# Escorna_CPU_2_12.net
KiCad netlist of a schematic drawn in EAGLE
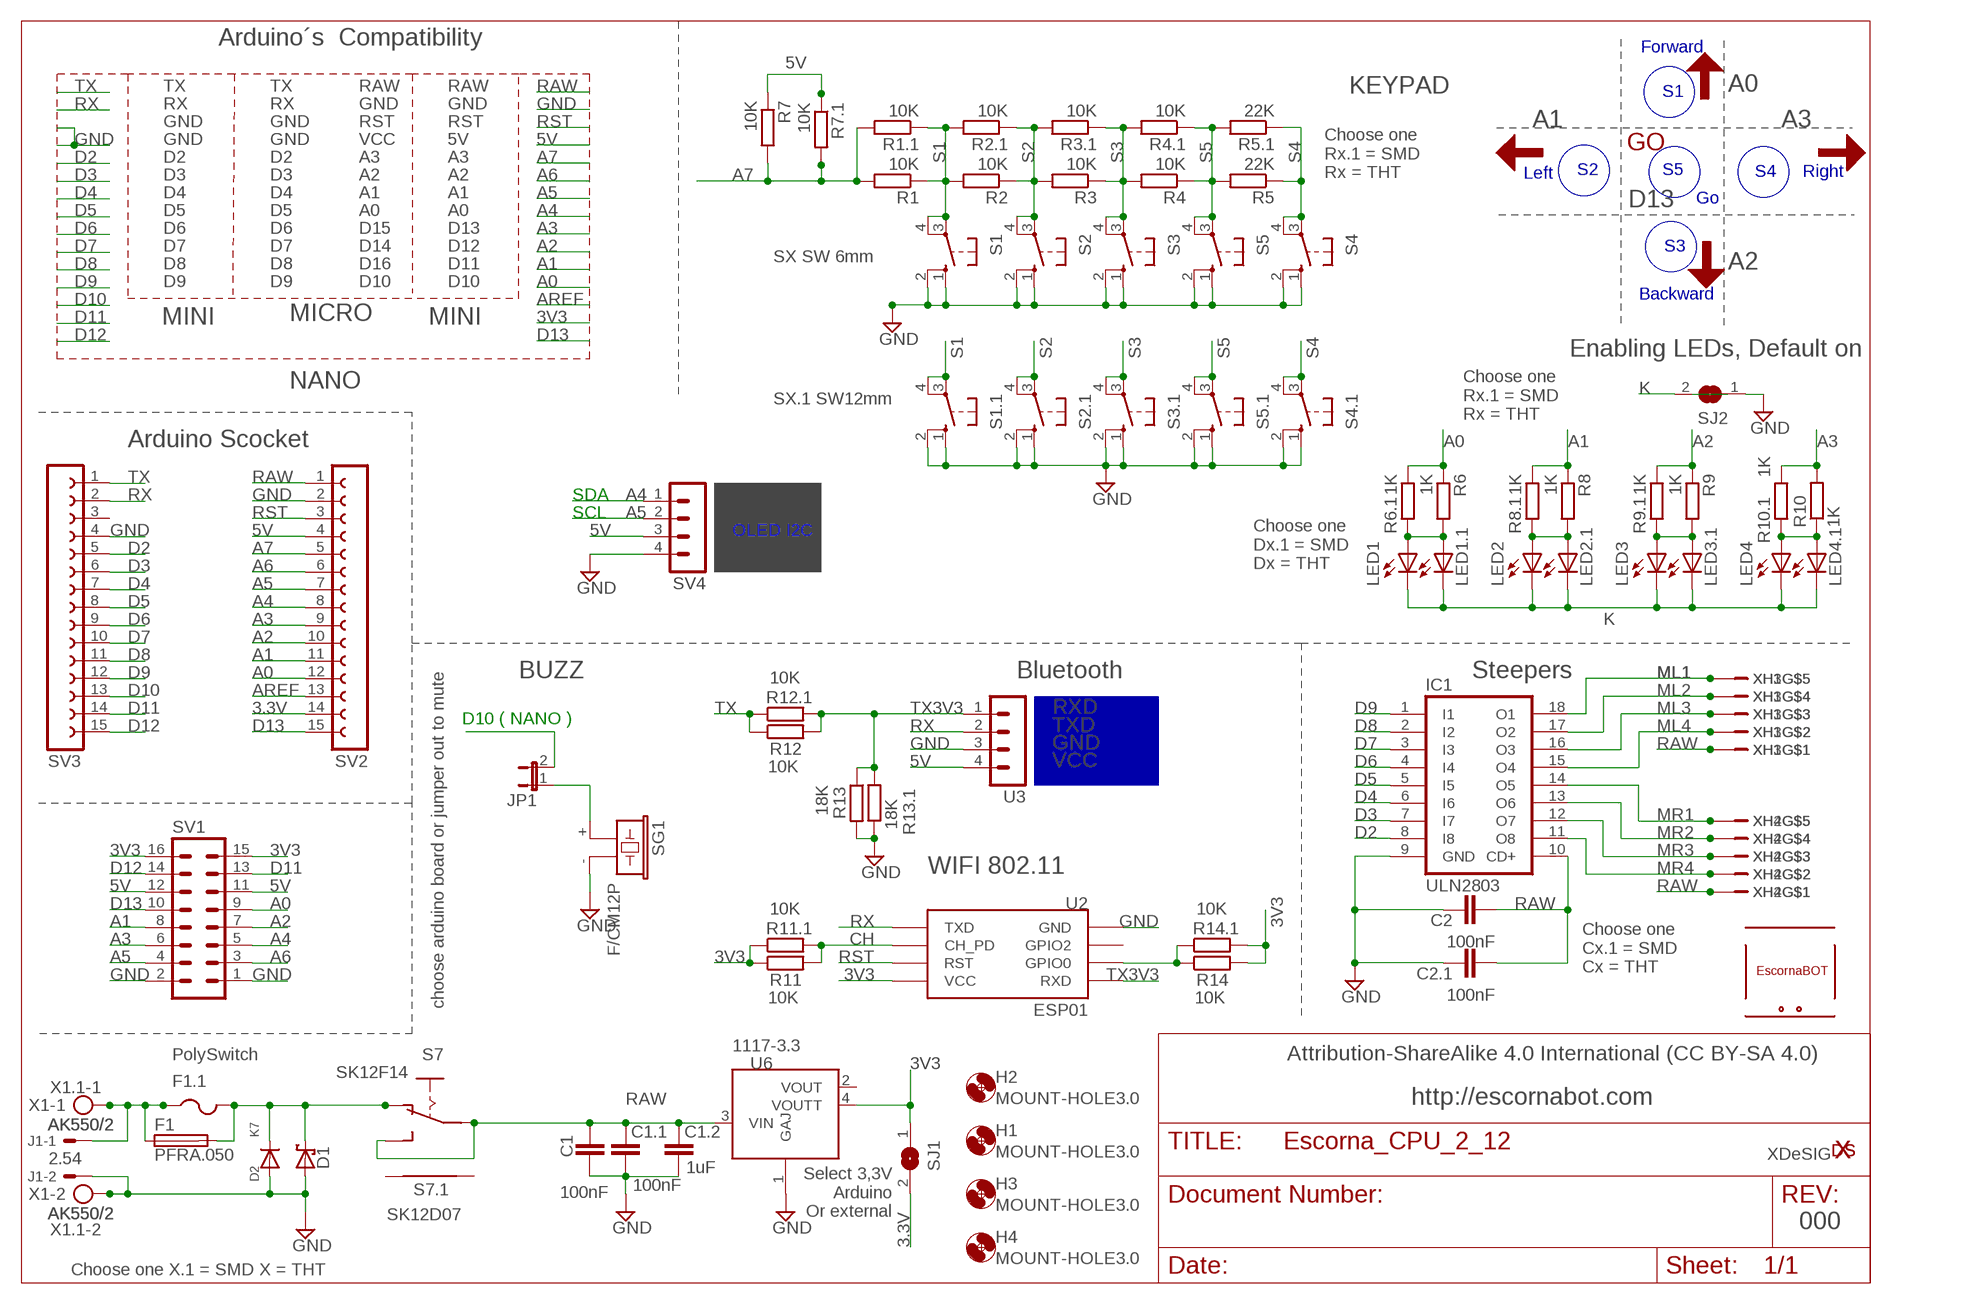
[diagram p0: schematic, sheet 1]

(export (version "E")
  (design (tool "Eeschema 10.0.6"))
  (components
    (comp (ref "C1")
      (value "100nF")
      (footprint "eagle-import:C025-025X050")
      (libsource (lib "eagle-import") (part "C-EU025-025X050"))
    )
    (comp (ref "C1.1")
      (value "100nF")
      (footprint "eagle-import:C1206")
      (libsource (lib "eagle-import") (part "C-EUC1206"))
    )
    (comp (ref "C1.2")
      (value "1uF")
      (footprint "eagle-import:C1206")
      (libsource (lib "eagle-import") (part "C-EUC1206"))
    )
    (comp (ref "C2")
      (value "100nF")
      (footprint "eagle-import:C025-025X050")
      (libsource (lib "eagle-import") (part "C-EU025-025X050"))
    )
    (comp (ref "C2.1")
      (value "100nF")
      (footprint "eagle-import:C1206")
      (libsource (lib "eagle-import") (part "C-EUC1206"))
    )
    (comp (ref "D1")
      (value "1N5817")
      (footprint "eagle-import:DO41-10")
      (libsource (lib "eagle-import") (part "P4KEXX"))
    )
    (comp (ref "D2")
      (value "K7")
      (footprint "eagle-import:SMADIODE")
      (libsource (lib "eagle-import") (part "DIODESMA"))
    )
    (comp (ref "ESC")
      (value "ESCORNABOT")
      (footprint "eagle-import:ESCORNA_PEQUE")
      (libsource (lib "eagle-import") (part "ESCORNABOT"))
    )
    (comp (ref "F1")
      (value "PFRA.050")
      (footprint "eagle-import:TE5")
      (libsource (lib "eagle-import") (part "FUSETE5"))
    )
    (comp (ref "F1.1")
      (value "PolySwitch")
      (footprint "eagle-import:R1206")
      (libsource (lib "eagle-import") (part "PTCFUSE-1206"))
    )
    (comp (ref "H1")
      (value "MOUNT-HOLE3.0")
      (footprint "eagle-import:3,0")
      (libsource (lib "eagle-import") (part "MOUNT-HOLE3.0"))
    )
    (comp (ref "H2")
      (value "MOUNT-HOLE3.0")
      (footprint "eagle-import:3,0")
      (libsource (lib "eagle-import") (part "MOUNT-HOLE3.0"))
    )
    (comp (ref "H3")
      (value "MOUNT-HOLE3.0")
      (footprint "eagle-import:3,0")
      (libsource (lib "eagle-import") (part "MOUNT-HOLE3.0"))
    )
    (comp (ref "H4")
      (value "MOUNT-HOLE3.0")
      (footprint "eagle-import:3,0")
      (libsource (lib "eagle-import") (part "MOUNT-HOLE3.0"))
    )
    (comp (ref "IC1")
      (value "ULN2803")
      (footprint "eagle-import:DIL18")
      (libsource (lib "eagle-import") (part "ULN2803A"))
    )
    (comp (ref "J1")
      (value "2.54")
      (footprint "eagle-import:6410-02")
      (libsource (lib "eagle-import") (part "22-?-0227-2021"))
    )
    (comp (ref "JP1")
      (value "JP1E")
      (footprint "eagle-import:JP1")
      (libsource (lib "eagle-import") (part "JP1E"))
    )
    (comp (ref "LED1")
      (value "LED3MM")
      (footprint "eagle-import:LED3MM")
      (libsource (lib "eagle-import") (part "LED3MM"))
    )
    (comp (ref "LED1.1")
      (value "LEDCHIPLED_0603")
      (footprint "eagle-import:CHIPLED_0603")
      (libsource (lib "eagle-import") (part "LEDCHIPLED_0603"))
    )
    (comp (ref "LED2")
      (value "LED3MM")
      (footprint "eagle-import:LED3MM")
      (libsource (lib "eagle-import") (part "LED3MM"))
    )
    (comp (ref "LED2.1")
      (value "LEDCHIPLED_0603")
      (footprint "eagle-import:CHIPLED_0603")
      (libsource (lib "eagle-import") (part "LEDCHIPLED_0603"))
    )
    (comp (ref "LED3")
      (value "LED3MM")
      (footprint "eagle-import:LED3MM")
      (libsource (lib "eagle-import") (part "LED3MM"))
    )
    (comp (ref "LED3.1")
      (value "LEDCHIPLED_0603")
      (footprint "eagle-import:CHIPLED_0603")
      (libsource (lib "eagle-import") (part "LEDCHIPLED_0603"))
    )
    (comp (ref "LED4")
      (value "LED3MM")
      (footprint "eagle-import:LED3MM")
      (libsource (lib "eagle-import") (part "LED3MM"))
    )
    (comp (ref "LED4.1")
      (value "LEDCHIPLED_0603")
      (footprint "eagle-import:CHIPLED_0603")
      (libsource (lib "eagle-import") (part "LEDCHIPLED_0603"))
    )
    (comp (ref "R1")
      (value "10K")
      (footprint "eagle-import:0204_7")
      (libsource (lib "eagle-import") (part "R-EU_0204/7"))
    )
    (comp (ref "R1.1")
      (value "10K")
      (footprint "eagle-import:R0603")
      (libsource (lib "eagle-import") (part "R-EU_R0603"))
    )
    (comp (ref "R2")
      (value "10K")
      (footprint "eagle-import:0204_7")
      (libsource (lib "eagle-import") (part "R-EU_0204/7"))
    )
    (comp (ref "R2.1")
      (value "10K")
      (footprint "eagle-import:R0603")
      (libsource (lib "eagle-import") (part "R-EU_R0603"))
    )
    (comp (ref "R3")
      (value "10K")
      (footprint "eagle-import:0204_7")
      (libsource (lib "eagle-import") (part "R-EU_0204/7"))
    )
    (comp (ref "R3.1")
      (value "10K")
      (footprint "eagle-import:R0603")
      (libsource (lib "eagle-import") (part "R-EU_R0603"))
    )
    (comp (ref "R4")
      (value "10K")
      (footprint "eagle-import:0204_7")
      (libsource (lib "eagle-import") (part "R-EU_0204/7"))
    )
    (comp (ref "R4.1")
      (value "10K")
      (footprint "eagle-import:R0603")
      (libsource (lib "eagle-import") (part "R-EU_R0603"))
    )
    (comp (ref "R5")
      (value "22K")
      (footprint "eagle-import:0204_7")
      (libsource (lib "eagle-import") (part "R-EU_0204/7"))
    )
    (comp (ref "R5.1")
      (value "22K")
      (footprint "eagle-import:R0603")
      (libsource (lib "eagle-import") (part "R-EU_R0603"))
    )
    (comp (ref "R6")
      (value "1K")
      (footprint "eagle-import:0204_7")
      (libsource (lib "eagle-import") (part "R-EU_0204/7"))
    )
    (comp (ref "R6.1")
      (value "1K")
      (footprint "eagle-import:R0603")
      (libsource (lib "eagle-import") (part "R-EU_R0603"))
    )
    (comp (ref "R7")
      (value "10K")
      (footprint "eagle-import:0204_7")
      (libsource (lib "eagle-import") (part "R-EU_0204/7"))
    )
    (comp (ref "R7.1")
      (value "10K")
      (footprint "eagle-import:R0603")
      (libsource (lib "eagle-import") (part "R-EU_R0603"))
    )
    (comp (ref "R8")
      (value "1K")
      (footprint "eagle-import:0204_7")
      (libsource (lib "eagle-import") (part "R-EU_0204/7"))
    )
    (comp (ref "R8.1")
      (value "1K")
      (footprint "eagle-import:R0603")
      (libsource (lib "eagle-import") (part "R-EU_R0603"))
    )
    (comp (ref "R9")
      (value "1K")
      (footprint "eagle-import:0204_7")
      (libsource (lib "eagle-import") (part "R-EU_0204/7"))
    )
    (comp (ref "R9.1")
      (value "1K")
      (footprint "eagle-import:R0603")
      (libsource (lib "eagle-import") (part "R-EU_R0603"))
    )
    (comp (ref "R10")
      (value "1K")
      (footprint "eagle-import:0204_7")
      (libsource (lib "eagle-import") (part "R-EU_0204/7"))
    )
    (comp (ref "R10.1")
      (value "1K")
      (footprint "eagle-import:R0603")
      (libsource (lib "eagle-import") (part "R-EU_R0603"))
    )
    (comp (ref "R11")
      (value "10K")
      (footprint "eagle-import:0204_7")
      (libsource (lib "eagle-import") (part "R-EU_0204/7"))
    )
    (comp (ref "R11.1")
      (value "10K")
      (footprint "eagle-import:R0603")
      (libsource (lib "eagle-import") (part "R-EU_R0603"))
    )
    (comp (ref "R12")
      (value "10K")
      (footprint "eagle-import:0204_7")
      (libsource (lib "eagle-import") (part "R-EU_0204/7"))
    )
    (comp (ref "R12.1")
      (value "10K")
      (footprint "eagle-import:R0603")
      (libsource (lib "eagle-import") (part "R-EU_R0603"))
    )
    (comp (ref "R13")
      (value "18K")
      (footprint "eagle-import:0204_7")
      (libsource (lib "eagle-import") (part "R-EU_0204/7"))
    )
    (comp (ref "R13.1")
      (value "18K")
      (footprint "eagle-import:R0603")
      (libsource (lib "eagle-import") (part "R-EU_R0603"))
    )
    (comp (ref "R14")
      (value "10K")
      (footprint "eagle-import:0204_7")
      (libsource (lib "eagle-import") (part "R-EU_0204/7"))
    )
    (comp (ref "R14.1")
      (value "10K")
      (footprint "eagle-import:R0603")
      (libsource (lib "eagle-import") (part "R-EU_R0603"))
    )
    (comp (ref "S1")
      (value "10-XX")
      (footprint "eagle-import:B3F-10XX")
      (fields (field (name "MPN") "B3F-1000"))
      (libsource (lib "eagle-import") (part "10-XX"))
    )
    (comp (ref "S1.1")
      (value "40-XX")
      (footprint "eagle-import:B3F-40XX")
      (fields (field (name "MF") "OMRON COMPONENTS USA") (field (name "MPN") "B3F-4000"))
      (libsource (lib "eagle-import") (part "40-XX"))
    )
    (comp (ref "S2")
      (value "10-XX")
      (footprint "eagle-import:B3F-10XX")
      (fields (field (name "MPN") "B3F-1000"))
      (libsource (lib "eagle-import") (part "10-XX"))
    )
    (comp (ref "S2.1")
      (value "40-XX")
      (footprint "eagle-import:B3F-40XX")
      (fields (field (name "MF") "OMRON COMPONENTS USA") (field (name "MPN") "B3F-4000"))
      (libsource (lib "eagle-import") (part "40-XX"))
    )
    (comp (ref "S3")
      (value "10-XX")
      (footprint "eagle-import:B3F-10XX")
      (fields (field (name "MPN") "B3F-1000"))
      (libsource (lib "eagle-import") (part "10-XX"))
    )
    (comp (ref "S3.1")
      (value "40-XX")
      (footprint "eagle-import:B3F-40XX")
      (fields (field (name "MF") "OMRON COMPONENTS USA") (field (name "MPN") "B3F-4000"))
      (libsource (lib "eagle-import") (part "40-XX"))
    )
    (comp (ref "S4")
      (value "10-XX")
      (footprint "eagle-import:B3F-10XX")
      (fields (field (name "MPN") "B3F-1000"))
      (libsource (lib "eagle-import") (part "10-XX"))
    )
    (comp (ref "S4.1")
      (value "40-XX")
      (footprint "eagle-import:B3F-40XX")
      (fields (field (name "MF") "OMRON COMPONENTS USA") (field (name "MPN") "B3F-4000"))
      (libsource (lib "eagle-import") (part "40-XX"))
    )
    (comp (ref "S5")
      (value "10-XX")
      (footprint "eagle-import:B3F-10XX")
      (fields (field (name "MPN") "B3F-1000"))
      (libsource (lib "eagle-import") (part "10-XX"))
    )
    (comp (ref "S5.1")
      (value "40-XX")
      (footprint "eagle-import:B3F-40XX")
      (fields (field (name "MF") "OMRON COMPONENTS USA") (field (name "MPN") "B3F-4000"))
      (libsource (lib "eagle-import") (part "40-XX"))
    )
    (comp (ref "S7")
      (value "SK12F14")
      (footprint "eagle-import:ESCORNA_SK-12F14-G")
      (libsource (lib "eagle-import") (part "ESCORNA_SK12F14F"))
    )
    (comp (ref "S7.1")
      (value "SK12D07")
      (footprint "eagle-import:ESCORNA_SK-12D07")
      (libsource (lib "eagle-import") (part "ESCORNA_SK12F14D"))
    )
    (comp (ref "SG1")
      (value "F/CM12P")
      (footprint "eagle-import:F_CM12P")
      (libsource (lib "eagle-import") (part "F/CM12P"))
    )
    (comp (ref "SJ1") (value "SJ") (footprint "eagle-import:SJ") (libsource (lib "eagle-import") (part "SJ")))
    (comp (ref "SJ2") (value "SJ") (footprint "eagle-import:SJ") (libsource (lib "eagle-import") (part "SJ")))
    (comp (ref "SV1")
      (value "MA08-2")
      (footprint "eagle-import:MA08-2")
      (libsource (lib "eagle-import") (part "MA08-2"))
    )
    (comp (ref "SV2")
      (value "CON-LSTA_FE15-1")
      (footprint "eagle-import:CON-LSTA_FE15")
      (libsource (lib "eagle-import") (part "CON-LSTA_FE15-1"))
    )
    (comp (ref "SV3")
      (value "CON-LSTA_FE15-1")
      (footprint "eagle-import:CON-LSTA_FE15")
      (libsource (lib "eagle-import") (part "CON-LSTA_FE15-1"))
    )
    (comp (ref "SV4")
      (value "MA04-1")
      (footprint "eagle-import:MA04-1")
      (libsource (lib "eagle-import") (part "MA04-1"))
    )
    (comp (ref "U$1")
      (value "FRECHA")
      (footprint "eagle-import:FRECHA")
      (libsource (lib "eagle-import") (part "FRECHA"))
    )
    (comp (ref "U$2")
      (value "GO")
      (footprint "eagle-import:VALE")
      (libsource (lib "eagle-import") (part "GO"))
    )
    (comp (ref "U$3")
      (value "FRECHA")
      (footprint "eagle-import:FRECHA")
      (libsource (lib "eagle-import") (part "FRECHA"))
    )
    (comp (ref "U$6")
      (value "FRECHA")
      (footprint "eagle-import:FRECHA")
      (libsource (lib "eagle-import") (part "FRECHA"))
    )
    (comp (ref "U$11")
      (value "FRECHA")
      (footprint "eagle-import:FRECHA")
      (libsource (lib "eagle-import") (part "FRECHA"))
    )
    (comp (ref "U$13")
      (value "XDESIG_XDESIG21")
      (footprint "eagle-import:XDESIG_XDESIG")
      (libsource (lib "eagle-import") (part "XDESIG_XDESIG21"))
    )
    (comp (ref "U2")
      (value "ESP01")
      (footprint "eagle-import:ESP01")
      (libsource (lib "eagle-import") (part "ESP01"))
    )
    (comp (ref "U3")
      (value "MA04-1")
      (footprint "eagle-import:MA04-1")
      (libsource (lib "eagle-import") (part "MA04-1"))
    )
    (comp (ref "U6")
      (value "1117-3.3")
      (footprint "eagle-import:SOT223")
      (libsource (lib "eagle-import") (part "ASM1117-3.3"))
    )
    (comp (ref "X1")
      (value "AK550/2")
      (footprint "eagle-import:AK550_2")
      (libsource (lib "eagle-import") (part "AK550/2"))
    )
    (comp (ref "X1.1")
      (value "AK550/2")
      (footprint "eagle-import:AK550_2")
      (fields (field (name "OC_FARNELL") "unknown") (field (name "OC_NEWARK") "unknown"))
      (libsource (lib "eagle-import") (part "AK550/2"))
    )
    (comp (ref "XDS1")
      (value "XDESIG")
      (footprint "eagle-import:XDESIG_CU_2")
      (libsource (lib "eagle-import") (part "XDESIG"))
    )
    (comp (ref "XH1")
      (value "B5B-XH-A")
      (footprint "eagle-import:B5B-XH-A")
      (libsource (lib "eagle-import") (part "B5B-XH-A"))
    )
    (comp (ref "XH2")
      (value "B5B-XH-A")
      (footprint "eagle-import:B5B-XH-A")
      (libsource (lib "eagle-import") (part "B5B-XH-A"))
    )
    (comp (ref "XH3")
      (value "B5B-XH-A")
      (footprint "eagle-import:B5B-XH-A")
      (libsource (lib "eagle-import") (part "B5B-XH-A"))
    )
    (comp (ref "XH4")
      (value "B5B-XH-A")
      (footprint "eagle-import:B5B-XH-A")
      (libsource (lib "eagle-import") (part "B5B-XH-A"))
    )
  )
  (nets
    (net (code "1") (name "/3.3V") (class "Default")
      (node (ref "SJ1") (pin "2") (pinfunction "2_2") (pintype "passive"))
      (node (ref "SV2") (pin "14") (pinfunction "14_14") (pintype "passive"))
    )
    (net (code "2") (name "/3V3") (class "Default")
      (node (ref "R11") (pin "1") (pinfunction "1_1") (pintype "passive"))
      (node (ref "R11.1") (pin "1") (pinfunction "1_1") (pintype "passive"))
      (node (ref "R14") (pin "2") (pinfunction "2_2") (pintype "passive"))
      (node (ref "R14.1") (pin "2") (pinfunction "2_2") (pintype "passive"))
      (node (ref "SJ1") (pin "1") (pinfunction "1_1") (pintype "passive"))
      (node (ref "SV1") (pin "15") (pinfunction "15_15") (pintype "passive"))
      (node (ref "SV1") (pin "16") (pinfunction "16_16") (pintype "passive"))
      (node (ref "U2") (pin "VCC") (pinfunction "VCC_VCC") (pintype "bidirectional"))
      (node (ref "U6") (pin "4") (pinfunction "VOUTT_4") (pintype "bidirectional"))
    )
    (net (code "3") (name "/5V") (class "Default")
      (node (ref "R7") (pin "1") (pinfunction "1_1") (pintype "passive"))
      (node (ref "R7.1") (pin "1") (pinfunction "1_1") (pintype "passive"))
      (node (ref "SV1") (pin "11") (pinfunction "11_11") (pintype "passive"))
      (node (ref "SV1") (pin "12") (pinfunction "12_12") (pintype "passive"))
      (node (ref "SV2") (pin "4") (pinfunction "4_4") (pintype "passive"))
      (node (ref "SV4") (pin "3") (pinfunction "3_3") (pintype "passive"))
      (node (ref "U3") (pin "4") (pinfunction "4_4") (pintype "passive"))
    )
    (net (code "4") (name "/A0") (class "Default")
      (node (ref "R6") (pin "1") (pinfunction "1_1") (pintype "passive"))
      (node (ref "R6.1") (pin "1") (pinfunction "1_1") (pintype "passive"))
      (node (ref "SV1") (pin "9") (pinfunction "9_9") (pintype "passive"))
      (node (ref "SV2") (pin "12") (pinfunction "12_12") (pintype "passive"))
    )
    (net (code "5") (name "/A1") (class "Default")
      (node (ref "R8") (pin "1") (pinfunction "1_1") (pintype "passive"))
      (node (ref "R8.1") (pin "1") (pinfunction "1_1") (pintype "passive"))
      (node (ref "SV1") (pin "8") (pinfunction "8_8") (pintype "passive"))
      (node (ref "SV2") (pin "11") (pinfunction "11_11") (pintype "passive"))
    )
    (net (code "6") (name "/A2") (class "Default")
      (node (ref "R9") (pin "1") (pinfunction "1_1") (pintype "passive"))
      (node (ref "R9.1") (pin "1") (pinfunction "1_1") (pintype "passive"))
      (node (ref "SV1") (pin "7") (pinfunction "7_7") (pintype "passive"))
      (node (ref "SV2") (pin "10") (pinfunction "10_10") (pintype "passive"))
    )
    (net (code "7") (name "/A3") (class "Default")
      (node (ref "R10") (pin "2") (pinfunction "2_2") (pintype "passive"))
      (node (ref "R10.1") (pin "1") (pinfunction "1_1") (pintype "passive"))
      (node (ref "SV1") (pin "6") (pinfunction "6_6") (pintype "passive"))
      (node (ref "SV2") (pin "9") (pinfunction "9_9") (pintype "passive"))
    )
    (net (code "8") (name "/A4") (class "Default")
      (node (ref "SV1") (pin "5") (pinfunction "5_5") (pintype "passive"))
      (node (ref "SV2") (pin "8") (pinfunction "8_8") (pintype "passive"))
      (node (ref "SV4") (pin "1") (pinfunction "1_1") (pintype "passive"))
    )
    (net (code "9") (name "/A5") (class "Default")
      (node (ref "SV1") (pin "4") (pinfunction "4_4") (pintype "passive"))
      (node (ref "SV2") (pin "7") (pinfunction "7_7") (pintype "passive"))
      (node (ref "SV4") (pin "2") (pinfunction "2_2") (pintype "passive"))
    )
    (net (code "10") (name "/A6") (class "Default")
      (node (ref "SV1") (pin "3") (pinfunction "3_3") (pintype "passive"))
      (node (ref "SV2") (pin "6") (pinfunction "6_6") (pintype "passive"))
    )
    (net (code "11") (name "/A7") (class "Default")
      (node (ref "R1") (pin "2") (pinfunction "2_2") (pintype "passive"))
      (node (ref "R1.1") (pin "2") (pinfunction "2_2") (pintype "passive"))
      (node (ref "R7") (pin "2") (pinfunction "2_2") (pintype "passive"))
      (node (ref "R7.1") (pin "2") (pinfunction "2_2") (pintype "passive"))
      (node (ref "SV2") (pin "5") (pinfunction "5_5") (pintype "passive"))
    )
    (net (code "12") (name "/AREF") (class "Default")
      (node (ref "SV2") (pin "13") (pinfunction "13_13") (pintype "passive"))
    )
    (net (code "13") (name "/CH") (class "Default")
      (node (ref "R11") (pin "2") (pinfunction "2_2") (pintype "passive"))
      (node (ref "R11.1") (pin "2") (pinfunction "2_2") (pintype "passive"))
      (node (ref "U2") (pin "CH_PD") (pinfunction "CH_PD_CH_PD") (pintype "bidirectional"))
    )
    (net (code "14") (name "/D2") (class "Default")
      (node (ref "IC1") (pin "8") (pinfunction "I8_8") (pintype "input"))
      (node (ref "SV3") (pin "5") (pinfunction "5_5") (pintype "passive"))
    )
    (net (code "15") (name "/D3") (class "Default")
      (node (ref "IC1") (pin "7") (pinfunction "I7_7") (pintype "input"))
      (node (ref "SV3") (pin "6") (pinfunction "6_6") (pintype "passive"))
    )
    (net (code "16") (name "/D4") (class "Default")
      (node (ref "IC1") (pin "6") (pinfunction "I6_6") (pintype "input"))
      (node (ref "SV3") (pin "7") (pinfunction "7_7") (pintype "passive"))
    )
    (net (code "17") (name "/D5") (class "Default")
      (node (ref "IC1") (pin "5") (pinfunction "I5_5") (pintype "input"))
      (node (ref "SV3") (pin "8") (pinfunction "8_8") (pintype "passive"))
    )
    (net (code "18") (name "/D6") (class "Default")
      (node (ref "IC1") (pin "4") (pinfunction "I4_4") (pintype "input"))
      (node (ref "SV3") (pin "9") (pinfunction "9_9") (pintype "passive"))
    )
    (net (code "19") (name "/D7") (class "Default")
      (node (ref "IC1") (pin "3") (pinfunction "I3_3") (pintype "input"))
      (node (ref "SV3") (pin "10") (pinfunction "10_10") (pintype "passive"))
    )
    (net (code "20") (name "/D8") (class "Default")
      (node (ref "IC1") (pin "2") (pinfunction "I2_2") (pintype "input"))
      (node (ref "SV3") (pin "11") (pinfunction "11_11") (pintype "passive"))
    )
    (net (code "21") (name "/D9") (class "Default")
      (node (ref "IC1") (pin "1") (pinfunction "I1_1") (pintype "input"))
      (node (ref "SV3") (pin "12") (pinfunction "12_12") (pintype "passive"))
    )
    (net (code "22") (name "/D10") (class "Default")
      (node (ref "JP1") (pin "2") (pinfunction "2_2") (pintype "passive"))
      (node (ref "SV3") (pin "13") (pinfunction "13_13") (pintype "passive"))
    )
    (net (code "23") (name "/D11") (class "Default")
      (node (ref "SV1") (pin "13") (pinfunction "13_13") (pintype "passive"))
      (node (ref "SV3") (pin "14") (pinfunction "14_14") (pintype "passive"))
    )
    (net (code "24") (name "/D12") (class "Default")
      (node (ref "SV1") (pin "14") (pinfunction "14_14") (pintype "passive"))
      (node (ref "SV3") (pin "15") (pinfunction "15_15") (pintype "passive"))
    )
    (net (code "25") (name "/D13") (class "Default")
      (node (ref "SV1") (pin "10") (pinfunction "10_10") (pintype "passive"))
      (node (ref "SV2") (pin "15") (pinfunction "15_15") (pintype "passive"))
    )
    (net (code "26") (name "/K") (class "Default")
      (node (ref "LED1") (pin "K") (pinfunction "C_K") (pintype "passive"))
      (node (ref "LED1.1") (pin "C") (pinfunction "C_C") (pintype "passive"))
      (node (ref "LED2") (pin "K") (pinfunction "C_K") (pintype "passive"))
      (node (ref "LED2.1") (pin "C") (pinfunction "C_C") (pintype "passive"))
      (node (ref "LED3") (pin "K") (pinfunction "C_K") (pintype "passive"))
      (node (ref "LED3.1") (pin "C") (pinfunction "C_C") (pintype "passive"))
      (node (ref "LED4") (pin "K") (pinfunction "C_K") (pintype "passive"))
      (node (ref "LED4.1") (pin "C") (pinfunction "C_C") (pintype "passive"))
      (node (ref "SJ2") (pin "2") (pinfunction "2_2") (pintype "passive"))
    )
    (net (code "27") (name "/ML1") (class "Default")
      (node (ref "IC1") (pin "18") (pinfunction "O1_18") (pintype "open_collector"))
      (node (ref "XH1") (pin "P$5") (pinfunction "1_P$5") (pintype "passive"))
      (node (ref "XH3") (pin "P$5") (pinfunction "1_P$5") (pintype "passive"))
    )
    (net (code "28") (name "/ML2") (class "Default")
      (node (ref "IC1") (pin "17") (pinfunction "O2_17") (pintype "open_collector"))
      (node (ref "XH1") (pin "P$4") (pinfunction "1_P$4") (pintype "passive"))
      (node (ref "XH3") (pin "P$4") (pinfunction "1_P$4") (pintype "passive"))
    )
    (net (code "29") (name "/ML3") (class "Default")
      (node (ref "IC1") (pin "16") (pinfunction "O3_16") (pintype "open_collector"))
      (node (ref "XH1") (pin "P$3") (pinfunction "1_P$3") (pintype "passive"))
      (node (ref "XH3") (pin "P$3") (pinfunction "1_P$3") (pintype "passive"))
    )
    (net (code "30") (name "/ML4") (class "Default")
      (node (ref "IC1") (pin "15") (pinfunction "O4_15") (pintype "open_collector"))
      (node (ref "XH1") (pin "P$2") (pinfunction "1_P$2") (pintype "passive"))
      (node (ref "XH3") (pin "P$2") (pinfunction "1_P$2") (pintype "passive"))
    )
    (net (code "31") (name "/MR1") (class "Default")
      (node (ref "IC1") (pin "14") (pinfunction "O5_14") (pintype "open_collector"))
      (node (ref "XH2") (pin "P$5") (pinfunction "1_P$5") (pintype "passive"))
      (node (ref "XH4") (pin "P$5") (pinfunction "1_P$5") (pintype "passive"))
    )
    (net (code "32") (name "/MR2") (class "Default")
      (node (ref "IC1") (pin "13") (pinfunction "O6_13") (pintype "open_collector"))
      (node (ref "XH2") (pin "P$4") (pinfunction "1_P$4") (pintype "passive"))
      (node (ref "XH4") (pin "P$4") (pinfunction "1_P$4") (pintype "passive"))
    )
    (net (code "33") (name "/MR3") (class "Default")
      (node (ref "IC1") (pin "12") (pinfunction "O7_12") (pintype "open_collector"))
      (node (ref "XH2") (pin "P$3") (pinfunction "1_P$3") (pintype "passive"))
      (node (ref "XH4") (pin "P$3") (pinfunction "1_P$3") (pintype "passive"))
    )
    (net (code "34") (name "/MR4") (class "Default")
      (node (ref "IC1") (pin "11") (pinfunction "O8_11") (pintype "open_collector"))
      (node (ref "XH2") (pin "P$2") (pinfunction "1_P$2") (pintype "passive"))
      (node (ref "XH4") (pin "P$2") (pinfunction "1_P$2") (pintype "passive"))
    )
    (net (code "35") (name "/RAW") (class "Default")
      (node (ref "C1") (pin "2") (pinfunction "2_2") (pintype "passive"))
      (node (ref "C1.1") (pin "2") (pinfunction "2_2") (pintype "passive"))
      (node (ref "C1.2") (pin "2") (pinfunction "2_2") (pintype "passive"))
      (node (ref "C2") (pin "2") (pinfunction "2_2") (pintype "passive"))
      (node (ref "C2.1") (pin "2") (pinfunction "2_2") (pintype "passive"))
      (node (ref "IC1") (pin "10") (pinfunction "CD+_10") (pintype "passive"))
      (node (ref "S7") (pin "P$1") (pinfunction "P_P$1") (pintype "passive"))
      (node (ref "S7") (pin "P$3") (pinfunction "S_P$3") (pintype "passive"))
      (node (ref "S7.1") (pin "P$1") (pinfunction "P_P$1") (pintype "passive"))
      (node (ref "S7.1") (pin "P$3") (pinfunction "S_P$3") (pintype "passive"))
      (node (ref "SV2") (pin "1") (pinfunction "1_1") (pintype "passive"))
      (node (ref "U6") (pin "3") (pinfunction "VIN_3") (pintype "bidirectional"))
      (node (ref "XH1") (pin "P$1") (pinfunction "1_P$1") (pintype "passive"))
      (node (ref "XH2") (pin "P$1") (pinfunction "1_P$1") (pintype "passive"))
      (node (ref "XH3") (pin "P$1") (pinfunction "1_P$1") (pintype "passive"))
      (node (ref "XH4") (pin "P$1") (pinfunction "1_P$1") (pintype "passive"))
    )
    (net (code "36") (name "/RST") (class "Default")
      (node (ref "SV2") (pin "3") (pinfunction "3_3") (pintype "passive"))
      (node (ref "U2") (pin "RST") (pinfunction "RST_RST") (pintype "bidirectional"))
    )
    (net (code "37") (name "/RX") (class "Default")
      (node (ref "SV3") (pin "2") (pinfunction "2_2") (pintype "passive"))
      (node (ref "U2") (pin "TX") (pinfunction "TXD_TX") (pintype "bidirectional"))
      (node (ref "U3") (pin "2") (pinfunction "2_2") (pintype "passive"))
    )
    (net (code "38") (name "/S1") (class "Default")
      (node (ref "R1") (pin "1") (pinfunction "1_1") (pintype "passive"))
      (node (ref "R1.1") (pin "1") (pinfunction "1_1") (pintype "passive"))
      (node (ref "R2") (pin "2") (pinfunction "2_2") (pintype "passive"))
      (node (ref "R2.1") (pin "2") (pinfunction "2_2") (pintype "passive"))
      (node (ref "S1") (pin "3") (pinfunction "P_3") (pintype "passive"))
      (node (ref "S1") (pin "4") (pinfunction "P1_4") (pintype "passive"))
      (node (ref "S1.1") (pin "3") (pinfunction "P_3") (pintype "passive"))
      (node (ref "S1.1") (pin "4") (pinfunction "P1_4") (pintype "passive"))
    )
    (net (code "39") (name "/S2") (class "Default")
      (node (ref "R2") (pin "1") (pinfunction "1_1") (pintype "passive"))
      (node (ref "R2.1") (pin "1") (pinfunction "1_1") (pintype "passive"))
      (node (ref "R3") (pin "2") (pinfunction "2_2") (pintype "passive"))
      (node (ref "R3.1") (pin "2") (pinfunction "2_2") (pintype "passive"))
      (node (ref "S2") (pin "3") (pinfunction "P_3") (pintype "passive"))
      (node (ref "S2") (pin "4") (pinfunction "P1_4") (pintype "passive"))
      (node (ref "S2.1") (pin "3") (pinfunction "P_3") (pintype "passive"))
      (node (ref "S2.1") (pin "4") (pinfunction "P1_4") (pintype "passive"))
    )
    (net (code "40") (name "/S3") (class "Default")
      (node (ref "R3") (pin "1") (pinfunction "1_1") (pintype "passive"))
      (node (ref "R3.1") (pin "1") (pinfunction "1_1") (pintype "passive"))
      (node (ref "R4") (pin "2") (pinfunction "2_2") (pintype "passive"))
      (node (ref "R4.1") (pin "2") (pinfunction "2_2") (pintype "passive"))
      (node (ref "S3") (pin "3") (pinfunction "P_3") (pintype "passive"))
      (node (ref "S3") (pin "4") (pinfunction "P1_4") (pintype "passive"))
      (node (ref "S3.1") (pin "3") (pinfunction "P_3") (pintype "passive"))
      (node (ref "S3.1") (pin "4") (pinfunction "P1_4") (pintype "passive"))
    )
    (net (code "41") (name "/S4") (class "Default")
      (node (ref "R5") (pin "1") (pinfunction "1_1") (pintype "passive"))
      (node (ref "R5.1") (pin "1") (pinfunction "1_1") (pintype "passive"))
      (node (ref "S4") (pin "3") (pinfunction "P_3") (pintype "passive"))
      (node (ref "S4") (pin "4") (pinfunction "P1_4") (pintype "passive"))
      (node (ref "S4.1") (pin "3") (pinfunction "P_3") (pintype "passive"))
      (node (ref "S4.1") (pin "4") (pinfunction "P1_4") (pintype "passive"))
    )
    (net (code "42") (name "/S5") (class "Default")
      (node (ref "R4") (pin "1") (pinfunction "1_1") (pintype "passive"))
      (node (ref "R4.1") (pin "1") (pinfunction "1_1") (pintype "passive"))
      (node (ref "R5") (pin "2") (pinfunction "2_2") (pintype "passive"))
      (node (ref "R5.1") (pin "2") (pinfunction "2_2") (pintype "passive"))
      (node (ref "S5") (pin "3") (pinfunction "P_3") (pintype "passive"))
      (node (ref "S5") (pin "4") (pinfunction "P1_4") (pintype "passive"))
      (node (ref "S5.1") (pin "3") (pinfunction "P_3") (pintype "passive"))
      (node (ref "S5.1") (pin "4") (pinfunction "P1_4") (pintype "passive"))
    )
    (net (code "43") (name "/TX") (class "Default")
      (node (ref "R12") (pin "1") (pinfunction "1_1") (pintype "passive"))
      (node (ref "R12.1") (pin "1") (pinfunction "1_1") (pintype "passive"))
      (node (ref "SV3") (pin "1") (pinfunction "1_1") (pintype "passive"))
    )
    (net (code "44") (name "/TX3V3") (class "Default")
      (node (ref "R12") (pin "2") (pinfunction "2_2") (pintype "passive"))
      (node (ref "R12.1") (pin "2") (pinfunction "2_2") (pintype "passive"))
      (node (ref "R13") (pin "1") (pinfunction "1_1") (pintype "passive"))
      (node (ref "R13.1") (pin "2") (pinfunction "2_2") (pintype "passive"))
      (node (ref "U2") (pin "RX") (pinfunction "RXD_RX") (pintype "bidirectional"))
      (node (ref "U3") (pin "1") (pinfunction "1_1") (pintype "passive"))
    )
    (net (code "45") (name "GND") (class "Default")
      (node (ref "C1") (pin "1") (pinfunction "1_1") (pintype "passive"))
      (node (ref "C1.1") (pin "1") (pinfunction "1_1") (pintype "passive"))
      (node (ref "C1.2") (pin "1") (pinfunction "1_1") (pintype "passive"))
      (node (ref "C2") (pin "1") (pinfunction "1_1") (pintype "passive"))
      (node (ref "C2.1") (pin "1") (pinfunction "1_1") (pintype "passive"))
      (node (ref "D1") (pin "A") (pinfunction "A_A") (pintype "passive"))
      (node (ref "D2") (pin "A") (pinfunction "A_A") (pintype "passive"))
      (node (ref "IC1") (pin "9") (pinfunction "GND_9") (pintype "power_in"))
      (node (ref "J1") (pin "2") (pinfunction "S_2") (pintype "passive"))
      (node (ref "R13") (pin "2") (pinfunction "2_2") (pintype "passive"))
      (node (ref "R13.1") (pin "1") (pinfunction "1_1") (pintype "passive"))
      (node (ref "S1") (pin "1") (pinfunction "S_1") (pintype "passive"))
      (node (ref "S1") (pin "2") (pinfunction "S1_2") (pintype "passive"))
      (node (ref "S1.1") (pin "1") (pinfunction "S_1") (pintype "passive"))
      (node (ref "S1.1") (pin "2") (pinfunction "S1_2") (pintype "passive"))
      (node (ref "S2") (pin "1") (pinfunction "S_1") (pintype "passive"))
      (node (ref "S2") (pin "2") (pinfunction "S1_2") (pintype "passive"))
      (node (ref "S2.1") (pin "1") (pinfunction "S_1") (pintype "passive"))
      (node (ref "S2.1") (pin "2") (pinfunction "S1_2") (pintype "passive"))
      (node (ref "S3") (pin "1") (pinfunction "S_1") (pintype "passive"))
      (node (ref "S3") (pin "2") (pinfunction "S1_2") (pintype "passive"))
      (node (ref "S3.1") (pin "1") (pinfunction "S_1") (pintype "passive"))
      (node (ref "S3.1") (pin "2") (pinfunction "S1_2") (pintype "passive"))
      (node (ref "S4") (pin "1") (pinfunction "S_1") (pintype "passive"))
      (node (ref "S4") (pin "2") (pinfunction "S1_2") (pintype "passive"))
      (node (ref "S4.1") (pin "1") (pinfunction "S_1") (pintype "passive"))
      (node (ref "S4.1") (pin "2") (pinfunction "S1_2") (pintype "passive"))
      (node (ref "S5") (pin "1") (pinfunction "S_1") (pintype "passive"))
      (node (ref "S5") (pin "2") (pinfunction "S1_2") (pintype "passive"))
      (node (ref "S5.1") (pin "1") (pinfunction "S_1") (pintype "passive"))
      (node (ref "S5.1") (pin "2") (pinfunction "S1_2") (pintype "passive"))
      (node (ref "SG1") (pin "-") (pinfunction "2_-") (pintype "passive"))
      (node (ref "SJ2") (pin "1") (pinfunction "1_1") (pintype "passive"))
      (node (ref "SV1") (pin "1") (pinfunction "1_1") (pintype "passive"))
      (node (ref "SV1") (pin "2") (pinfunction "2_2") (pintype "passive"))
      (node (ref "SV2") (pin "2") (pinfunction "2_2") (pintype "passive"))
      (node (ref "SV3") (pin "4") (pinfunction "4_4") (pintype "passive"))
      (node (ref "SV4") (pin "4") (pinfunction "4_4") (pintype "passive"))
      (node (ref "U2") (pin "GND") (pinfunction "GND_GND") (pintype "bidirectional"))
      (node (ref "U3") (pin "3") (pinfunction "3_3") (pintype "passive"))
      (node (ref "U6") (pin "1") (pinfunction "GAJ_1") (pintype "bidirectional"))
      (node (ref "X1") (pin "2") (pinfunction "KL_2") (pintype "passive"))
      (node (ref "X1.1") (pin "2") (pinfunction "KL_2") (pintype "passive"))
    )
    (net (code "46") (name "Net-(J1A-S)") (class "Default")
      (node (ref "F1") (pin "1") (pinfunction "1_1") (pintype "passive"))
      (node (ref "F1.1") (pin "1") (pinfunction "1_1") (pintype "passive"))
      (node (ref "J1") (pin "1") (pinfunction "S_1") (pintype "passive"))
      (node (ref "X1") (pin "1") (pinfunction "KL_1") (pintype "passive"))
      (node (ref "X1.1") (pin "1") (pinfunction "KL_1") (pintype "passive"))
    )
    (net (code "47") (name "Net-(LED1-PadA)") (class "Default")
      (node (ref "LED1") (pin "A") (pinfunction "A_A") (pintype "passive"))
      (node (ref "LED1.1") (pin "A") (pinfunction "A_A") (pintype "passive"))
      (node (ref "R6") (pin "2") (pinfunction "2_2") (pintype "passive"))
      (node (ref "R6.1") (pin "2") (pinfunction "2_2") (pintype "passive"))
    )
    (net (code "48") (name "Net-(LED2-PadA)") (class "Default")
      (node (ref "LED2") (pin "A") (pinfunction "A_A") (pintype "passive"))
      (node (ref "LED2.1") (pin "A") (pinfunction "A_A") (pintype "passive"))
      (node (ref "R8") (pin "2") (pinfunction "2_2") (pintype "passive"))
      (node (ref "R8.1") (pin "2") (pinfunction "2_2") (pintype "passive"))
    )
    (net (code "49") (name "Net-(LED3-PadA)") (class "Default")
      (node (ref "LED3") (pin "A") (pinfunction "A_A") (pintype "passive"))
      (node (ref "LED3.1") (pin "A") (pinfunction "A_A") (pintype "passive"))
      (node (ref "R9") (pin "2") (pinfunction "2_2") (pintype "passive"))
      (node (ref "R9.1") (pin "2") (pinfunction "2_2") (pintype "passive"))
    )
    (net (code "50") (name "Net-(LED4-PadA)") (class "Default")
      (node (ref "LED4") (pin "A") (pinfunction "A_A") (pintype "passive"))
      (node (ref "LED4.1") (pin "A") (pinfunction "A_A") (pintype "passive"))
      (node (ref "R10") (pin "1") (pinfunction "1_1") (pintype "passive"))
      (node (ref "R10.1") (pin "2") (pinfunction "2_2") (pintype "passive"))
    )
    (net (code "51") (name "Net-(R14-Pad1)") (class "Default")
      (node (ref "R14") (pin "1") (pinfunction "1_1") (pintype "passive"))
      (node (ref "R14.1") (pin "1") (pinfunction "1_1") (pintype "passive"))
      (node (ref "U2") (pin "GPIO0") (pinfunction "GPIO0_GPIO0") (pintype "bidirectional"))
    )
    (net (code "52") (name "Net-(S7-O)") (class "Default")
      (node (ref "D1") (pin "C") (pinfunction "C_C") (pintype "passive"))
      (node (ref "D2") (pin "C") (pinfunction "C_C") (pintype "passive"))
      (node (ref "F1") (pin "2") (pinfunction "2_2") (pintype "passive"))
      (node (ref "F1.1") (pin "2") (pinfunction "2_2") (pintype "passive"))
      (node (ref "S7") (pin "P$2") (pinfunction "O_P$2") (pintype "passive"))
      (node (ref "S7.1") (pin "P$2") (pinfunction "O_P$2") (pintype "passive"))
    )
    (net (code "53") (name "Net-(S7-P$1)") (class "Default")
      (node (ref "S7") (pin "P$4") (pinfunction "P$1_P$4") (pintype "passive"))
      (node (ref "S7.1") (pin "P$4") (pinfunction "P$1_P$4") (pintype "passive"))
    )
    (net (code "54") (name "Net-(S7-P$2)") (class "Default")
      (node (ref "S7") (pin "P$5") (pinfunction "P$2_P$5") (pintype "bidirectional"))
      (node (ref "S7.1") (pin "P$5") (pinfunction "P$2_P$5") (pintype "bidirectional"))
    )
    (net (code "55") (name "Net-(SG1-1)") (class "Default")
      (node (ref "JP1") (pin "1") (pinfunction "1_1") (pintype "passive"))
      (node (ref "SG1") (pin "+") (pinfunction "1_+") (pintype "passive"))
    )
    (net (code "56") (name "unconnected-(SV3-Pad3)") (class "Default")
      (node (ref "SV3") (pin "3") (pinfunction "3_3") (pintype "passive"))
    )
    (net (code "57") (name "unconnected-(U2-PadGPIO2)") (class "Default")
      (node (ref "U2") (pin "GPIO2") (pinfunction "GPIO2_GPIO2") (pintype "bidirectional"))
    )
    (net (code "58") (name "unconnected-(U6-VOUT-Pad2)") (class "Default")
      (node (ref "U6") (pin "2") (pinfunction "VOUT_2") (pintype "bidirectional"))
    )
  )
)
